# BarRange.net
KiCad netlist of a schematic drawn in EAGLE
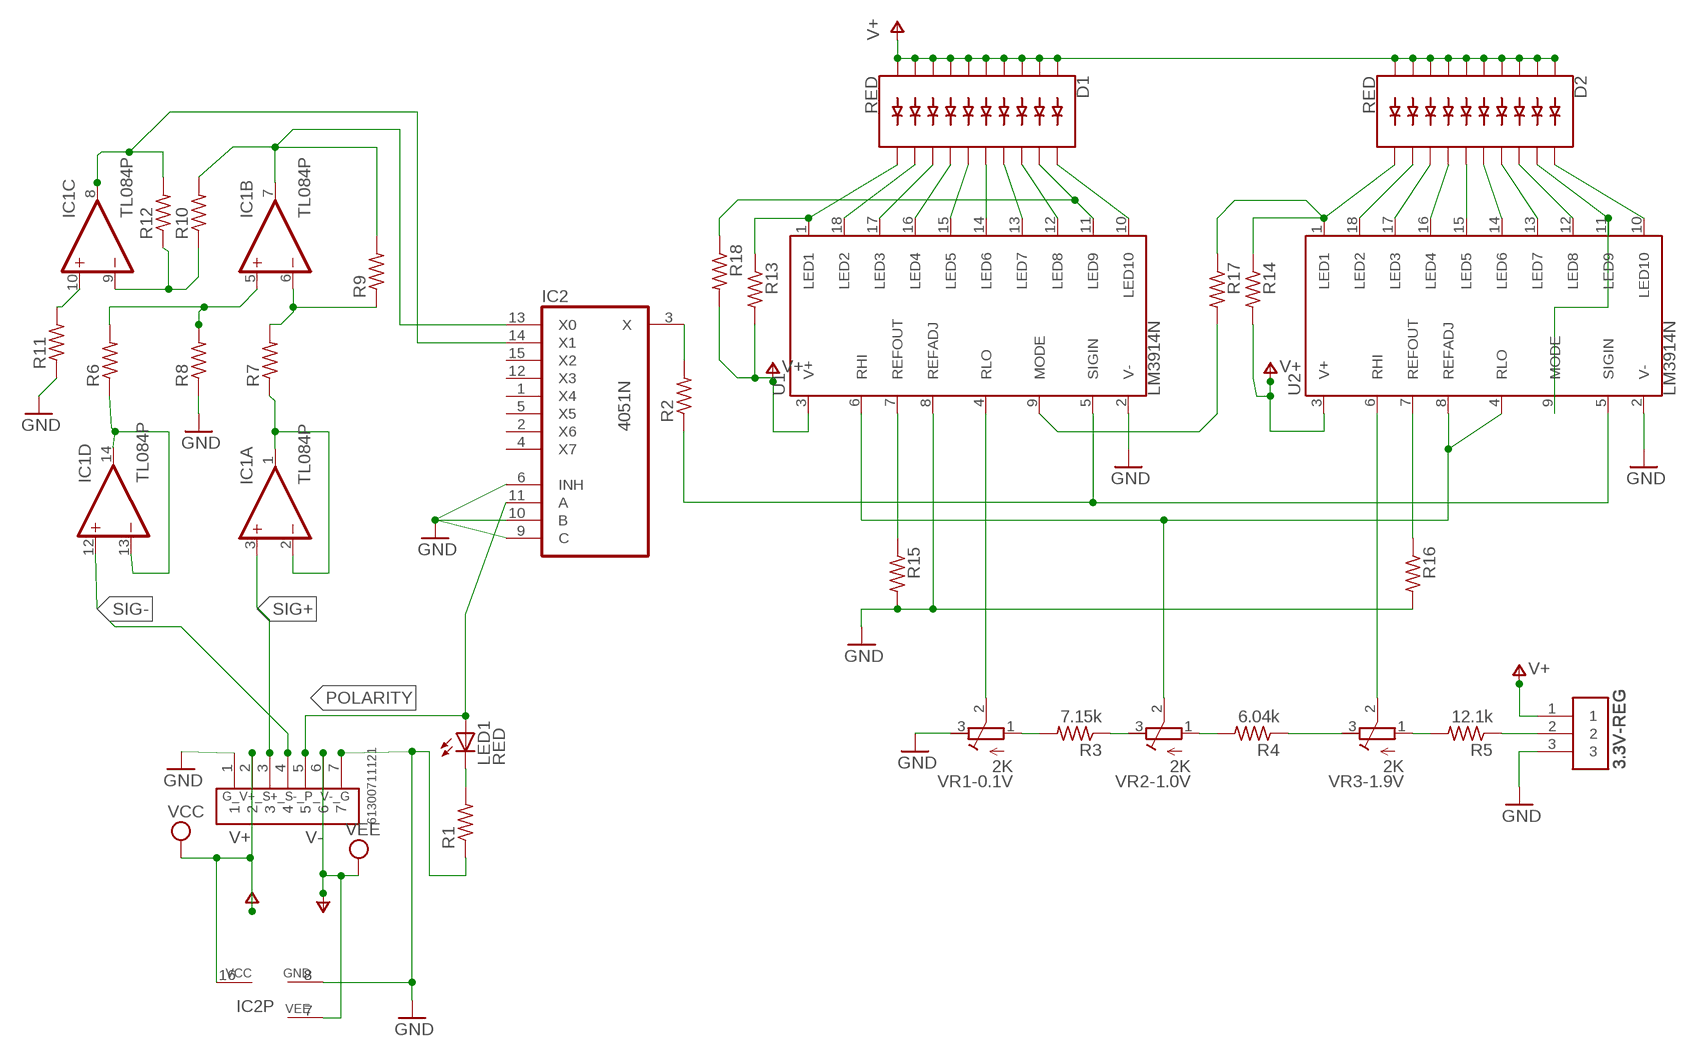
[diagram p0: schematic, sheet 1]

(export (version "E")
  (design (tool "Eeschema 10.0.6"))
  (components
    (comp (ref "3.3V-REG")
      (value "3.3V-REG")
      (footprint "eagle-import:61300311121")
      (fields
        (field (name "DIGI_KEY_PART_NUMBER") "732-5316-ND")
        (field (name "MANUFACTURER") "Wurth Electronics Inc.")
        (field (name "MPN") "61300311121")
        (field (name "CREATED_BY") "PCBLayout.com")
      )
      (libsource (lib "eagle-import") (part "61300311121"))
    )
    (comp (ref "D1")
      (value "RED")
      (footprint "eagle-import:LED_BARGRAPH_10")
      (libsource (lib "eagle-import") (part "LED_BARGRAPH_10RED"))
    )
    (comp (ref "D2")
      (value "RED")
      (footprint "eagle-import:LED_BARGRAPH_10")
      (libsource (lib "eagle-import") (part "LED_BARGRAPH_10RED"))
    )
    (comp (ref "G_V+_S+_S-_P_V-_G")
      (value "61300711121")
      (footprint "eagle-import:61300711121")
      (fields
        (field (name "DIGI_KEY_PART_NUMBER") "732-5320-ND")
        (field (name "MANUFACTURER") "Wurth Electronics Inc.")
        (field (name "CREATED_BY") "PCBLayout.com")
      )
      (libsource (lib "eagle-import") (part "61300711121"))
    )
    (comp (ref "IC1")
      (value "TL084P")
      (footprint "eagle-import:DIL14")
      (libsource (lib "eagle-import") (part "TL084P"))
    )
    (comp (ref "IC2")
      (value "4051N")
      (footprint "eagle-import:DIL16")
      (libsource (lib "eagle-import") (part "4051N"))
    )
    (comp (ref "LED1")
      (value "RED")
      (footprint "eagle-import:LED5MM")
      (libsource (lib "eagle-import") (part "LED5MM"))
    )
    (comp (ref "R1")
      (value "R-US_0204/7")
      (footprint "eagle-import:0204_7")
      (libsource (lib "eagle-import") (part "R-US_0204/7"))
    )
    (comp (ref "R2")
      (value "R-US_0204/7")
      (footprint "eagle-import:0204_7")
      (libsource (lib "eagle-import") (part "R-US_0204/7"))
    )
    (comp (ref "R3")
      (value "7.15k")
      (footprint "eagle-import:0204_7")
      (libsource (lib "eagle-import") (part "R-US_0204/7"))
    )
    (comp (ref "R4")
      (value "6.04k")
      (footprint "eagle-import:0204_7")
      (libsource (lib "eagle-import") (part "R-US_0204/7"))
    )
    (comp (ref "R5")
      (value "12.1k")
      (footprint "eagle-import:0204_7")
      (libsource (lib "eagle-import") (part "R-US_0204/7"))
    )
    (comp (ref "R6")
      (value "R-US_0204/7")
      (footprint "eagle-import:0204_7")
      (libsource (lib "eagle-import") (part "R-US_0204/7"))
    )
    (comp (ref "R7")
      (value "R-US_0204/7")
      (footprint "eagle-import:0204_7")
      (libsource (lib "eagle-import") (part "R-US_0204/7"))
    )
    (comp (ref "R8")
      (value "R-US_0204/7")
      (footprint "eagle-import:0204_7")
      (libsource (lib "eagle-import") (part "R-US_0204/7"))
    )
    (comp (ref "R9")
      (value "R-US_0204/7")
      (footprint "eagle-import:0204_7")
      (libsource (lib "eagle-import") (part "R-US_0204/7"))
    )
    (comp (ref "R10")
      (value "R-US_0204/7")
      (footprint "eagle-import:0204_7")
      (libsource (lib "eagle-import") (part "R-US_0204/7"))
    )
    (comp (ref "R11")
      (value "R-US_0204/7")
      (footprint "eagle-import:0204_7")
      (libsource (lib "eagle-import") (part "R-US_0204/7"))
    )
    (comp (ref "R12")
      (value "R-US_0204/7")
      (footprint "eagle-import:0204_7")
      (libsource (lib "eagle-import") (part "R-US_0204/7"))
    )
    (comp (ref "R13")
      (value "R-US_0204/7")
      (footprint "eagle-import:0204_7")
      (libsource (lib "eagle-import") (part "R-US_0204/7"))
    )
    (comp (ref "R14")
      (value "R-US_0204/7")
      (footprint "eagle-import:0204_7")
      (libsource (lib "eagle-import") (part "R-US_0204/7"))
    )
    (comp (ref "R15")
      (value "R-US_0204/7")
      (footprint "eagle-import:0204_7")
      (libsource (lib "eagle-import") (part "R-US_0204/7"))
    )
    (comp (ref "R16")
      (value "R-US_0204/7")
      (footprint "eagle-import:0204_7")
      (libsource (lib "eagle-import") (part "R-US_0204/7"))
    )
    (comp (ref "R17")
      (value "R-US_0204/7")
      (footprint "eagle-import:0204_7")
      (libsource (lib "eagle-import") (part "R-US_0204/7"))
    )
    (comp (ref "R18")
      (value "R-US_0204/7")
      (footprint "eagle-import:0204_7")
      (libsource (lib "eagle-import") (part "R-US_0204/7"))
    )
    (comp (ref "U1")
      (value "LM3914N")
      (footprint "eagle-import:DIL18")
      (libsource (lib "eagle-import") (part "LM391N4"))
    )
    (comp (ref "U2")
      (value "LM3914N")
      (footprint "eagle-import:DIL18")
      (libsource (lib "eagle-import") (part "LM391N4"))
    )
    (comp (ref "VR1-0.1V")
      (value "2K")
      (footprint "eagle-import:RTRIM3299W")
      (libsource (lib "eagle-import") (part "R-TRIMM3299W"))
    )
    (comp (ref "VR2-1.0V")
      (value "2K")
      (footprint "eagle-import:RTRIM3299W")
      (libsource (lib "eagle-import") (part "R-TRIMM3299W"))
    )
    (comp (ref "VR3-1.9V")
      (value "2K")
      (footprint "eagle-import:RTRIM3299W")
      (libsource (lib "eagle-import") (part "R-TRIMM3299W"))
    )
  )
  (nets
    (net (code "1") (name "GND") (class "Default")
      (node (ref "3.3V-REG") (pin "3") (pinfunction "3_3") (pintype "passive"))
      (node (ref "G_V+_S+_S-_P_V-_G") (pin "1") (pinfunction "1_1") (pintype "passive"))
      (node (ref "G_V+_S+_S-_P_V-_G") (pin "7") (pinfunction "7_7") (pintype "passive"))
      (node (ref "IC2") (pin "10") (pinfunction "B_10") (pintype "input"))
      (node (ref "IC2") (pin "6") (pinfunction "INH_6") (pintype "input"))
      (node (ref "IC2") (pin "8") (pinfunction "GND_8") (pintype "power_in"))
      (node (ref "IC2") (pin "9") (pinfunction "C_9") (pintype "input"))
      (node (ref "R1") (pin "1") (pinfunction "1_1") (pintype "passive"))
      (node (ref "R11") (pin "1") (pinfunction "1_1") (pintype "passive"))
      (node (ref "R15") (pin "2") (pinfunction "2_2") (pintype "passive"))
      (node (ref "R16") (pin "2") (pinfunction "2_2") (pintype "passive"))
      (node (ref "R8") (pin "1") (pinfunction "1_1") (pintype "passive"))
      (node (ref "U1") (pin "2") (pinfunction "V-_2") (pintype "power_in"))
      (node (ref "U1") (pin "8") (pinfunction "REFADJ_8") (pintype "passive"))
      (node (ref "U2") (pin "2") (pinfunction "V-_2") (pintype "power_in"))
      (node (ref "VR1-0.1V") (pin "3") (pinfunction "E_3") (pintype "passive"))
    )
    (net (code "2") (name "Net-(3.3V-REG-Pad2)") (class "Default")
      (node (ref "3.3V-REG") (pin "2") (pinfunction "2_2") (pintype "passive"))
      (node (ref "R5") (pin "1") (pinfunction "1_1") (pintype "passive"))
    )
    (net (code "3") (name "Net-(D1-C)") (class "Default")
      (node (ref "D1") (pin "20") (pinfunction "C_20") (pintype "passive"))
      (node (ref "U1") (pin "10") (pinfunction "LED10_10") (pintype "output"))
    )
    (net (code "4") (name "Net-(D1-C1)") (class "Default")
      (node (ref "D1") (pin "19") (pinfunction "C1_19") (pintype "passive"))
      (node (ref "R18") (pin "1") (pinfunction "1_1") (pintype "passive"))
      (node (ref "U1") (pin "11") (pinfunction "LED9_11") (pintype "output"))
    )
    (net (code "5") (name "Net-(D1-C2)") (class "Default")
      (node (ref "D1") (pin "18") (pinfunction "C2_18") (pintype "passive"))
      (node (ref "U1") (pin "12") (pinfunction "LED8_12") (pintype "output"))
    )
    (net (code "6") (name "Net-(D1-C3)") (class "Default")
      (node (ref "D1") (pin "17") (pinfunction "C3_17") (pintype "passive"))
      (node (ref "U1") (pin "13") (pinfunction "LED7_13") (pintype "output"))
    )
    (net (code "7") (name "Net-(D1-C4)") (class "Default")
      (node (ref "D1") (pin "16") (pinfunction "C4_16") (pintype "passive"))
      (node (ref "U1") (pin "14") (pinfunction "LED6_14") (pintype "output"))
    )
    (net (code "8") (name "Net-(D1-C5)") (class "Default")
      (node (ref "D1") (pin "15") (pinfunction "C5_15") (pintype "passive"))
      (node (ref "U1") (pin "15") (pinfunction "LED5_15") (pintype "output"))
    )
    (net (code "9") (name "Net-(D1-C6)") (class "Default")
      (node (ref "D1") (pin "14") (pinfunction "C6_14") (pintype "passive"))
      (node (ref "U1") (pin "16") (pinfunction "LED4_16") (pintype "output"))
    )
    (net (code "10") (name "Net-(D1-C7)") (class "Default")
      (node (ref "D1") (pin "13") (pinfunction "C7_13") (pintype "passive"))
      (node (ref "U1") (pin "17") (pinfunction "LED3_17") (pintype "output"))
    )
    (net (code "11") (name "Net-(D1-C8)") (class "Default")
      (node (ref "D1") (pin "12") (pinfunction "C8_12") (pintype "passive"))
      (node (ref "U1") (pin "18") (pinfunction "LED2_18") (pintype "output"))
    )
    (net (code "12") (name "Net-(D1-C9)") (class "Default")
      (node (ref "D1") (pin "11") (pinfunction "C9_11") (pintype "passive"))
      (node (ref "R13") (pin "1") (pinfunction "1_1") (pintype "passive"))
      (node (ref "U1") (pin "1") (pinfunction "LED1_1") (pintype "output"))
    )
    (net (code "13") (name "Net-(D2-C)") (class "Default")
      (node (ref "D2") (pin "20") (pinfunction "C_20") (pintype "passive"))
      (node (ref "U2") (pin "10") (pinfunction "LED10_10") (pintype "output"))
    )
    (net (code "14") (name "Net-(D2-C1)") (class "Default")
      (node (ref "D2") (pin "19") (pinfunction "C1_19") (pintype "passive"))
      (node (ref "U2") (pin "11") (pinfunction "LED9_11") (pintype "output"))
      (node (ref "U2") (pin "9") (pinfunction "MODE_9") (pintype "input"))
    )
    (net (code "15") (name "Net-(D2-C2)") (class "Default")
      (node (ref "D2") (pin "18") (pinfunction "C2_18") (pintype "passive"))
      (node (ref "U2") (pin "12") (pinfunction "LED8_12") (pintype "output"))
    )
    (net (code "16") (name "Net-(D2-C3)") (class "Default")
      (node (ref "D2") (pin "17") (pinfunction "C3_17") (pintype "passive"))
      (node (ref "U2") (pin "13") (pinfunction "LED7_13") (pintype "output"))
    )
    (net (code "17") (name "Net-(D2-C4)") (class "Default")
      (node (ref "D2") (pin "16") (pinfunction "C4_16") (pintype "passive"))
      (node (ref "U2") (pin "14") (pinfunction "LED6_14") (pintype "output"))
    )
    (net (code "18") (name "Net-(D2-C5)") (class "Default")
      (node (ref "D2") (pin "15") (pinfunction "C5_15") (pintype "passive"))
      (node (ref "U2") (pin "15") (pinfunction "LED5_15") (pintype "output"))
    )
    (net (code "19") (name "Net-(D2-C6)") (class "Default")
      (node (ref "D2") (pin "14") (pinfunction "C6_14") (pintype "passive"))
      (node (ref "U2") (pin "16") (pinfunction "LED4_16") (pintype "output"))
    )
    (net (code "20") (name "Net-(D2-C7)") (class "Default")
      (node (ref "D2") (pin "13") (pinfunction "C7_13") (pintype "passive"))
      (node (ref "U2") (pin "17") (pinfunction "LED3_17") (pintype "output"))
    )
    (net (code "21") (name "Net-(D2-C8)") (class "Default")
      (node (ref "D2") (pin "12") (pinfunction "C8_12") (pintype "passive"))
      (node (ref "U2") (pin "18") (pinfunction "LED2_18") (pintype "output"))
    )
    (net (code "22") (name "Net-(D2-C9)") (class "Default")
      (node (ref "D2") (pin "11") (pinfunction "C9_11") (pintype "passive"))
      (node (ref "R14") (pin "1") (pinfunction "1_1") (pintype "passive"))
      (node (ref "R17") (pin "1") (pinfunction "1_1") (pintype "passive"))
      (node (ref "U2") (pin "1") (pinfunction "LED1_1") (pintype "output"))
    )
    (net (code "23") (name "Net-(IC1A--IN)") (class "Default")
      (node (ref "IC1") (pin "1") (pinfunction "OUT_1") (pintype "output"))
      (node (ref "IC1") (pin "2") (pinfunction "-IN_2") (pintype "input"))
      (node (ref "R7") (pin "1") (pinfunction "1_1") (pintype "passive"))
    )
    (net (code "24") (name "Net-(IC1B-+IN)") (class "Default")
      (node (ref "IC1") (pin "5") (pinfunction "+IN_5") (pintype "input"))
      (node (ref "R6") (pin "2") (pinfunction "2_2") (pintype "passive"))
      (node (ref "R8") (pin "2") (pinfunction "2_2") (pintype "passive"))
    )
    (net (code "25") (name "Net-(IC1B--IN)") (class "Default")
      (node (ref "IC1") (pin "6") (pinfunction "-IN_6") (pintype "input"))
      (node (ref "R7") (pin "2") (pinfunction "2_2") (pintype "passive"))
      (node (ref "R9") (pin "1") (pinfunction "1_1") (pintype "passive"))
    )
    (net (code "26") (name "Net-(IC1B-OUT)") (class "Default")
      (node (ref "IC1") (pin "7") (pinfunction "OUT_7") (pintype "output"))
      (node (ref "IC2") (pin "13") (pinfunction "X0_13") (pintype "bidirectional"))
      (node (ref "R10") (pin "2") (pinfunction "2_2") (pintype "passive"))
      (node (ref "R9") (pin "2") (pinfunction "2_2") (pintype "passive"))
    )
    (net (code "27") (name "Net-(IC1C-+IN)") (class "Default")
      (node (ref "IC1") (pin "10") (pinfunction "+IN_10") (pintype "input"))
      (node (ref "R11") (pin "2") (pinfunction "2_2") (pintype "passive"))
    )
    (net (code "28") (name "Net-(IC1C--IN)") (class "Default")
      (node (ref "IC1") (pin "9") (pinfunction "-IN_9") (pintype "input"))
      (node (ref "R10") (pin "1") (pinfunction "1_1") (pintype "passive"))
      (node (ref "R12") (pin "1") (pinfunction "1_1") (pintype "passive"))
    )
    (net (code "29") (name "Net-(IC1C-OUT)") (class "Default")
      (node (ref "IC1") (pin "8") (pinfunction "OUT_8") (pintype "output"))
      (node (ref "IC2") (pin "14") (pinfunction "X1_14") (pintype "bidirectional"))
      (node (ref "R12") (pin "2") (pinfunction "2_2") (pintype "passive"))
    )
    (net (code "30") (name "Net-(IC1D--IN)") (class "Default")
      (node (ref "IC1") (pin "13") (pinfunction "-IN_13") (pintype "input"))
      (node (ref "IC1") (pin "14") (pinfunction "OUT_14") (pintype "output"))
      (node (ref "R6") (pin "1") (pinfunction "1_1") (pintype "passive"))
    )
    (net (code "31") (name "Net-(IC2A-X)") (class "Default")
      (node (ref "IC2") (pin "3") (pinfunction "X_3") (pintype "bidirectional"))
      (node (ref "R2") (pin "2") (pinfunction "2_2") (pintype "passive"))
    )
    (net (code "32") (name "Net-(LED1-C)") (class "Default")
      (node (ref "LED1") (pin "K") (pinfunction "C_K") (pintype "passive"))
      (node (ref "R1") (pin "2") (pinfunction "2_2") (pintype "passive"))
    )
    (net (code "33") (name "Net-(U1-MODE)") (class "Default")
      (node (ref "R17") (pin "2") (pinfunction "2_2") (pintype "passive"))
      (node (ref "U1") (pin "9") (pinfunction "MODE_9") (pintype "input"))
    )
    (net (code "34") (name "Net-(U1-REFOUT)") (class "Default")
      (node (ref "R15") (pin "1") (pinfunction "1_1") (pintype "passive"))
      (node (ref "U1") (pin "7") (pinfunction "REFOUT_7") (pintype "output"))
    )
    (net (code "35") (name "Net-(U1-RHI)") (class "Default")
      (node (ref "U1") (pin "6") (pinfunction "RHI_6") (pintype "input"))
      (node (ref "U2") (pin "4") (pinfunction "RLO_4") (pintype "input"))
      (node (ref "U2") (pin "8") (pinfunction "REFADJ_8") (pintype "passive"))
      (node (ref "VR2-1.0V") (pin "2") (pinfunction "S_2") (pintype "passive"))
    )
    (net (code "36") (name "Net-(U1-RLO)") (class "Default")
      (node (ref "U1") (pin "4") (pinfunction "RLO_4") (pintype "input"))
      (node (ref "VR1-0.1V") (pin "2") (pinfunction "S_2") (pintype "passive"))
    )
    (net (code "37") (name "Net-(U1-SIGIN)") (class "Default")
      (node (ref "R2") (pin "1") (pinfunction "1_1") (pintype "passive"))
      (node (ref "U1") (pin "5") (pinfunction "SIGIN_5") (pintype "input"))
      (node (ref "U2") (pin "5") (pinfunction "SIGIN_5") (pintype "input"))
    )
    (net (code "38") (name "Net-(U2-REFOUT)") (class "Default")
      (node (ref "R16") (pin "1") (pinfunction "1_1") (pintype "passive"))
      (node (ref "U2") (pin "7") (pinfunction "REFOUT_7") (pintype "output"))
    )
    (net (code "39") (name "Net-(U2-RHI)") (class "Default")
      (node (ref "U2") (pin "6") (pinfunction "RHI_6") (pintype "input"))
      (node (ref "VR3-1.9V") (pin "2") (pinfunction "S_2") (pintype "passive"))
    )
    (net (code "40") (name "Net-(VR1-0.1V-A)") (class "Default")
      (node (ref "R3") (pin "2") (pinfunction "2_2") (pintype "passive"))
      (node (ref "VR1-0.1V") (pin "1") (pinfunction "A_1") (pintype "passive"))
    )
    (net (code "41") (name "Net-(VR2-1.0V-A)") (class "Default")
      (node (ref "R4") (pin "2") (pinfunction "2_2") (pintype "passive"))
      (node (ref "VR2-1.0V") (pin "1") (pinfunction "A_1") (pintype "passive"))
    )
    (net (code "42") (name "Net-(VR2-1.0V-E)") (class "Default")
      (node (ref "R3") (pin "1") (pinfunction "1_1") (pintype "passive"))
      (node (ref "VR2-1.0V") (pin "3") (pinfunction "E_3") (pintype "passive"))
    )
    (net (code "43") (name "Net-(VR3-1.9V-A)") (class "Default")
      (node (ref "R5") (pin "2") (pinfunction "2_2") (pintype "passive"))
      (node (ref "VR3-1.9V") (pin "1") (pinfunction "A_1") (pintype "passive"))
    )
    (net (code "44") (name "Net-(VR3-1.9V-E)") (class "Default")
      (node (ref "R4") (pin "1") (pinfunction "1_1") (pintype "passive"))
      (node (ref "VR3-1.9V") (pin "3") (pinfunction "E_3") (pintype "passive"))
    )
    (net (code "45") (name "POLARITY") (class "Default")
      (node (ref "G_V+_S+_S-_P_V-_G") (pin "5") (pinfunction "5_5") (pintype "passive"))
      (node (ref "IC2") (pin "11") (pinfunction "A_11") (pintype "input"))
      (node (ref "LED1") (pin "A") (pinfunction "A_A") (pintype "passive"))
    )
    (net (code "46") (name "SIG+") (class "Default")
      (node (ref "G_V+_S+_S-_P_V-_G") (pin "3") (pinfunction "3_3") (pintype "passive"))
      (node (ref "IC1") (pin "3") (pinfunction "+IN_3") (pintype "input"))
    )
    (net (code "47") (name "SIG-") (class "Default")
      (node (ref "G_V+_S+_S-_P_V-_G") (pin "4") (pinfunction "4_4") (pintype "passive"))
      (node (ref "IC1") (pin "12") (pinfunction "+IN_12") (pintype "input"))
    )
    (net (code "48") (name "V+") (class "Default")
      (node (ref "3.3V-REG") (pin "1") (pinfunction "1_1") (pintype "passive"))
      (node (ref "D1") (pin "1") (pinfunction "A_1") (pintype "passive"))
      (node (ref "D1") (pin "10") (pinfunction "A9_10") (pintype "passive"))
      (node (ref "D1") (pin "2") (pinfunction "A1_2") (pintype "passive"))
      (node (ref "D1") (pin "3") (pinfunction "A2_3") (pintype "passive"))
      (node (ref "D1") (pin "4") (pinfunction "A3_4") (pintype "passive"))
      (node (ref "D1") (pin "5") (pinfunction "A4_5") (pintype "passive"))
      (node (ref "D1") (pin "6") (pinfunction "A5_6") (pintype "passive"))
      (node (ref "D1") (pin "7") (pinfunction "A6_7") (pintype "passive"))
      (node (ref "D1") (pin "8") (pinfunction "A7_8") (pintype "passive"))
      (node (ref "D1") (pin "9") (pinfunction "A8_9") (pintype "passive"))
      (node (ref "D2") (pin "1") (pinfunction "A_1") (pintype "passive"))
      (node (ref "D2") (pin "10") (pinfunction "A9_10") (pintype "passive"))
      (node (ref "D2") (pin "2") (pinfunction "A1_2") (pintype "passive"))
      (node (ref "D2") (pin "3") (pinfunction "A2_3") (pintype "passive"))
      (node (ref "D2") (pin "4") (pinfunction "A3_4") (pintype "passive"))
      (node (ref "D2") (pin "5") (pinfunction "A4_5") (pintype "passive"))
      (node (ref "D2") (pin "6") (pinfunction "A5_6") (pintype "passive"))
      (node (ref "D2") (pin "7") (pinfunction "A6_7") (pintype "passive"))
      (node (ref "D2") (pin "8") (pinfunction "A7_8") (pintype "passive"))
      (node (ref "D2") (pin "9") (pinfunction "A8_9") (pintype "passive"))
      (node (ref "G_V+_S+_S-_P_V-_G") (pin "2") (pinfunction "2_2") (pintype "passive"))
      (node (ref "IC2") (pin "16") (pinfunction "VCC_16") (pintype "power_in"))
      (node (ref "R13") (pin "2") (pinfunction "2_2") (pintype "passive"))
      (node (ref "R14") (pin "2") (pinfunction "2_2") (pintype "passive"))
      (node (ref "R18") (pin "2") (pinfunction "2_2") (pintype "passive"))
      (node (ref "U1") (pin "3") (pinfunction "V+_3") (pintype "power_in"))
      (node (ref "U2") (pin "3") (pinfunction "V+_3") (pintype "power_in"))
    )
    (net (code "49") (name "V-") (class "Default")
      (node (ref "G_V+_S+_S-_P_V-_G") (pin "6") (pinfunction "6_6") (pintype "passive"))
      (node (ref "IC2") (pin "7") (pinfunction "VEE_7") (pintype "power_in"))
    )
    (net (code "50") (name "unconnected-(IC2A-X2-Pad15)") (class "Default")
      (node (ref "IC2") (pin "15") (pinfunction "X2_15") (pintype "bidirectional"))
    )
    (net (code "51") (name "unconnected-(IC2A-X3-Pad12)") (class "Default")
      (node (ref "IC2") (pin "12") (pinfunction "X3_12") (pintype "bidirectional"))
    )
    (net (code "52") (name "unconnected-(IC2A-X4-Pad1)") (class "Default")
      (node (ref "IC2") (pin "1") (pinfunction "X4_1") (pintype "bidirectional"))
    )
    (net (code "53") (name "unconnected-(IC2A-X5-Pad5)") (class "Default")
      (node (ref "IC2") (pin "5") (pinfunction "X5_5") (pintype "bidirectional"))
    )
    (net (code "54") (name "unconnected-(IC2A-X6-Pad2)") (class "Default")
      (node (ref "IC2") (pin "2") (pinfunction "X6_2") (pintype "bidirectional"))
    )
    (net (code "55") (name "unconnected-(IC2A-X7-Pad4)") (class "Default")
      (node (ref "IC2") (pin "4") (pinfunction "X7_4") (pintype "bidirectional"))
    )
  )
)
